# PM12_LDO.net
KiCad netlist of a schematic drawn in Altium Designer
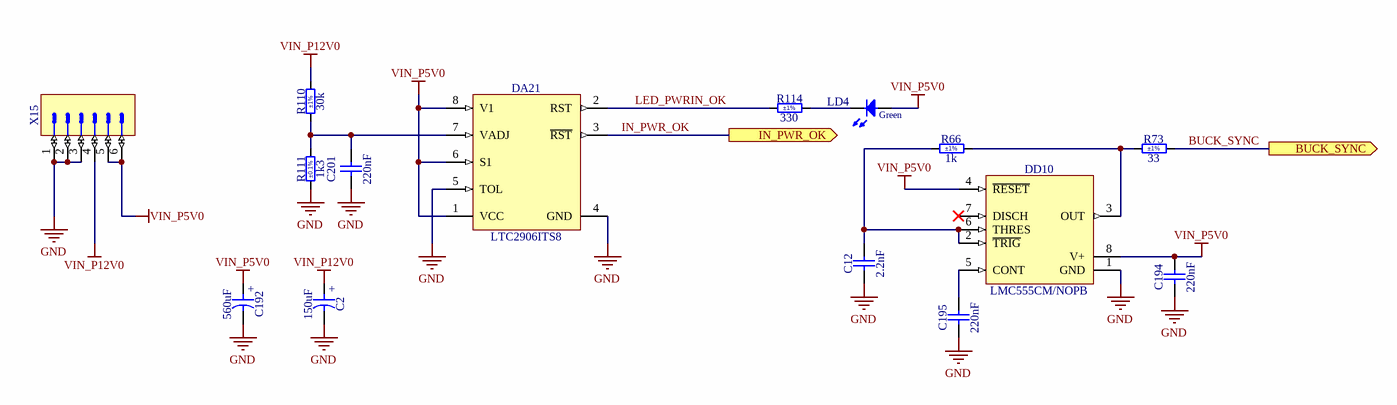
[diagram p0: PM12_LDO.SchDoc]

(export (version "E")
  (design (tool "Eeschema 10.0.6"))
  (components
    (comp (ref "C2")
      (value "150uF")
      (footprint "CAPAE830X1020N")
      (description "Polarised capacitor")
      (fields
        (field (name "PART NUMBER") "CAE830-1020_150UF_25V_20%")
        (field (name "VOLTAGE") "25V")
        (field (name "AUTHOR") "CERN DEM HF")
      )
      (libsource (lib "Capacitors") (part "Capacitor - polarized"))
    )
    (comp (ref "C12")
      (value "2.2nF")
      (footprint "CAPC2013X100N")
      (description "Non-polarised capacitor")
      (fields
        (field (name "PART NUMBER") "CC0805_2.2NF_50V_5%_C0G")
        (field (name "VOLTAGE") "50V")
        (field (name "AUTHOR") "CERN DEM MR")
      )
      (libsource (lib "Capacitors") (part "Capacitor - non polarized"))
    )
    (comp (ref "C192")
      (value "560uF")
      (footprint "CAPAE830X1020N")
      (description "Polarised capacitor")
      (fields
        (field (name "PART NUMBER") "CAE830-1020_560UF_10V_20%")
        (field (name "VOLTAGE") "10V")
        (field (name "AUTHOR") "CERN DEM HF")
      )
      (libsource (lib "Capacitors") (part "Capacitor - polarized"))
    )
    (comp (ref "C194")
      (value "220nF")
      (footprint "CAPC2012X135N")
      (description "Non-polarised capacitor")
      (fields
        (field (name "PART NUMBER") "CC0805_220NF_50V_10%_X7R")
        (field (name "VOLTAGE") "50V")
        (field (name "AUTHOR") "CERN DEM JLC")
      )
      (libsource (lib "Capacitors") (part "Capacitor - non polarized"))
    )
    (comp (ref "C195")
      (value "220nF")
      (footprint "CAPC2012X135N")
      (description "Non-polarised capacitor")
      (fields
        (field (name "PART NUMBER") "CC0805_220NF_50V_10%_X7R")
        (field (name "VOLTAGE") "50V")
        (field (name "AUTHOR") "CERN DEM JLC")
      )
      (libsource (lib "Capacitors") (part "Capacitor - non polarized"))
    )
    (comp (ref "C201")
      (value "220nF")
      (footprint "CAPC2012X135N")
      (description "Non-polarised capacitor")
      (fields
        (field (name "PART NUMBER") "CC0805_220NF_50V_10%_X7R")
        (field (name "VOLTAGE") "50V")
        (field (name "AUTHOR") "CERN DEM JLC")
      )
      (libsource (lib "Capacitors") (part "Capacitor - non polarized"))
    )
    (comp (ref "DA21")
      (value "LTC2906ITS8")
      (footprint "SOT65P280X100-8N")
      (description "Precision Dual Supply Monitors with One Pin-Selectable Threshold and One Adjustable Input")
      (fields (field (name "MANUFACTURER") "LINEAR TECHNOLOGY") (field (name "AUTHOR") "CERN DEM HF"))
      (libsource (lib "ICs And Semiconductors") (part "LTC2906xTS8"))
    )
    (comp (ref "DD10")
      (value "LMC555CM/NOPB")
      (footprint "SOIC127P600X175-8N")
      (description "CMOS Timer")
      (fields
        (field (name "MANUFACTURER") "NATIONAL SEMICONDUCTOR")
        (field (name "MANUFACTURER PART NUMBER") "LMC555CM")
        (field (name "AUTHOR") "CERN DEM JLC")
      )
      (libsource (lib "ICs And Semiconductors") (part "LMC555CM"))
    )
    (comp (ref "LD4")
      (value "Green")
      (footprint "LED_KINGBRIGHT_KPH-1608CGCK")
      (description "LED Green 1C 2A")
      (fields
        (field (name "PART NUMBER") "LED_KINGBRIGHT_KPH-1608CGCK")
        (field (name "MANUFACTURER") "KINGBRIGHT")
        (field (name "AUTHOR") "CERN DEM JLC")
      )
      (libsource (lib "ICs And Semiconductors") (part "LED Green 1C 2A"))
    )
    (comp (ref "R66")
      (value "1k")
      (footprint "RESC1005X40N")
      (description "Resistor - 1%")
      (fields
        (field (name "TOLERANCE") "±1%")
        (field (name "PART NUMBER") "R0402_1K_1%_0.0625W_100PPM")
        (field (name "POWER") "0.0625W")
        (field (name "AUTHOR") "CERN DEM JLC")
      )
      (libsource (lib "Resistors") (part "Resistor - 1%"))
    )
    (comp (ref "R73")
      (value "33")
      (footprint "RESC1005X40N")
      (description "Resistor - 1%")
      (fields
        (field (name "TOLERANCE") "±1%")
        (field (name "PART NUMBER") "R0402_33R_1%_0.0625W_100PPM")
        (field (name "POWER") "0.0625W")
        (field (name "AUTHOR") "CERN DEM JLC")
      )
      (libsource (lib "Resistors") (part "Resistor - 1%"))
    )
    (comp (ref "R110")
      (value "30k")
      (footprint "RESC2012X60N")
      (description "Resistor - 1%")
      (fields
        (field (name "TOLERANCE") "±1%")
        (field (name "PART NUMBER") "R0805_30K_1%_0.125W_100PPM")
        (field (name "POWER") "0.125W")
        (field (name "AUTHOR") "CERN DEM JLC")
      )
      (libsource (lib "Resistors") (part "Resistor - 1%"))
    )
    (comp (ref "R111")
      (value "1k3")
      (footprint "RESC2012X60N")
      (description "Resistor - 0.1%")
      (fields
        (field (name "TOLERANCE") "±0.1%")
        (field (name "PART NUMBER") "R0805_1K3_0.1%_0.1W_10PPM")
        (field (name "POWER") "0.1W")
        (field (name "AUTHOR") "CERN DEM JLC")
      )
      (libsource (lib "Resistors") (part "Resistor - 0.1%"))
    )
    (comp (ref "R114")
      (value "330")
      (footprint "RESC1005X40N")
      (description "Resistor - 1%")
      (fields
        (field (name "TOLERANCE") "±1%")
        (field (name "PART NUMBER") "R0402_330R_1%_0.0625W_100PPM")
        (field (name "POWER") "0.0625W")
        (field (name "AUTHOR") "CERN DEM JLC")
      )
      (libsource (lib "Resistors") (part "Resistor - 1%"))
    )
    (comp (ref "X15")
      (value "Mini-Fit BMI")
      (footprint "MOLEX_15-24-9067")
      (description "Connector 6 Male")
      (fields
        (field (name "PART NUMBER") "MOLEX_15-24-9067")
        (field (name "MANUFACTURER") "MOLEX")
        (field (name "AUTHOR") "CERN DEM HF")
      )
      (libsource (lib "Connectors") (part "Connector 6 Male"))
    )
  )
  (nets
    (net (code "1") (name "/BUCK_SYNC") (class "Default")
      (node (ref "R73") (pin "2") (pinfunction "2_2") (pintype "passive"))
    )
    (net (code "2") (name "/IN_PWR_OK") (class "Default")
      (node (ref "DA21") (pin "3") (pinfunction "~{RST}_3") (pintype "output"))
    )
    (net (code "3") (name "/LED_PWRIN_OK") (class "Default")
      (node (ref "DA21") (pin "2") (pinfunction "RST_2") (pintype "output"))
      (node (ref "R114") (pin "1") (pinfunction "1_1") (pintype "passive"))
    )
    (net (code "4") (name "GND") (class "Default")
      (node (ref "C12") (pin "1") (pinfunction "1_1") (pintype "passive"))
      (node (ref "C192") (pin "2") (pinfunction "2_2") (pintype "passive"))
      (node (ref "C194") (pin "1") (pinfunction "1_1") (pintype "passive"))
      (node (ref "C195") (pin "1") (pinfunction "1_1") (pintype "passive"))
      (node (ref "C2") (pin "2") (pinfunction "2_2") (pintype "passive"))
      (node (ref "C201") (pin "1") (pinfunction "1_1") (pintype "passive"))
      (node (ref "DA21") (pin "4") (pinfunction "GND_4") (pintype "power_in"))
      (node (ref "DA21") (pin "5") (pinfunction "TOL_5") (pintype "input"))
      (node (ref "DD10") (pin "1") (pinfunction "GND_1") (pintype "power_in"))
      (node (ref "R111") (pin "1") (pinfunction "1_1") (pintype "passive"))
      (node (ref "X15") (pin "1") (pinfunction "1_1") (pintype "bidirectional"))
      (node (ref "X15") (pin "2") (pinfunction "2_2") (pintype "bidirectional"))
      (node (ref "X15") (pin "3") (pinfunction "3_3") (pintype "bidirectional"))
    )
    (net (code "5") (name "Net-(DA21-VADJ)") (class "Default")
      (node (ref "C201") (pin "2") (pinfunction "2_2") (pintype "passive"))
      (node (ref "DA21") (pin "7") (pinfunction "VADJ_7") (pintype "input"))
      (node (ref "R110") (pin "1") (pinfunction "1_1") (pintype "passive"))
      (node (ref "R111") (pin "2") (pinfunction "2_2") (pintype "passive"))
    )
    (net (code "6") (name "Net-(DD10-CONT)") (class "Default")
      (node (ref "C195") (pin "2") (pinfunction "2_2") (pintype "passive"))
      (node (ref "DD10") (pin "5") (pinfunction "CONT_5") (pintype "input"))
    )
    (net (code "7") (name "Net-(DD10-OUT)") (class "Default")
      (node (ref "DD10") (pin "3") (pinfunction "OUT_3") (pintype "output"))
      (node (ref "R66") (pin "2") (pinfunction "2_2") (pintype "passive"))
      (node (ref "R73") (pin "1") (pinfunction "1_1") (pintype "passive"))
    )
    (net (code "8") (name "Net-(DD10-THRES)") (class "Default")
      (node (ref "C12") (pin "2") (pinfunction "2_2") (pintype "passive"))
      (node (ref "DD10") (pin "2") (pinfunction "~{TRIG}_2") (pintype "input"))
      (node (ref "DD10") (pin "6") (pinfunction "THRES_6") (pintype "input"))
      (node (ref "R66") (pin "1") (pinfunction "1_1") (pintype "passive"))
    )
    (net (code "9") (name "Net-(LD4-C)") (class "Default")
      (node (ref "LD4") (pin "1") (pinfunction "C_1") (pintype "passive"))
      (node (ref "R114") (pin "2") (pinfunction "2_2") (pintype "passive"))
    )
    (net (code "10") (name "VIN_P5V0") (class "Default")
      (node (ref "C192") (pin "1") (pinfunction "1_1") (pintype "passive"))
      (node (ref "C194") (pin "2") (pinfunction "2_2") (pintype "passive"))
      (node (ref "DA21") (pin "1") (pinfunction "VCC_1") (pintype "power_in"))
      (node (ref "DA21") (pin "6") (pinfunction "S1_6") (pintype "input"))
      (node (ref "DA21") (pin "8") (pinfunction "V1_8") (pintype "input"))
      (node (ref "DD10") (pin "4") (pinfunction "~{RESET}_4") (pintype "input"))
      (node (ref "DD10") (pin "8") (pinfunction "V+_8") (pintype "power_in"))
      (node (ref "LD4") (pin "2") (pinfunction "A_2") (pintype "passive"))
      (node (ref "X15") (pin "5") (pinfunction "5_5") (pintype "bidirectional"))
      (node (ref "X15") (pin "6") (pinfunction "6_6") (pintype "bidirectional"))
    )
    (net (code "11") (name "VIN_P12V0") (class "Default")
      (node (ref "C2") (pin "1") (pinfunction "1_1") (pintype "passive"))
      (node (ref "R110") (pin "2") (pinfunction "2_2") (pintype "passive"))
      (node (ref "X15") (pin "4") (pinfunction "4_4") (pintype "bidirectional"))
    )
    (net (code "12") (name "unconnected-(DD10-DISCH-Pad7)") (class "Default")
      (node (ref "DD10") (pin "7") (pinfunction "DISCH_7") (pintype "input+no_connect"))
    )
  )
)
